# TestRig.net
KiCad netlist of a schematic drawn in EAGLE
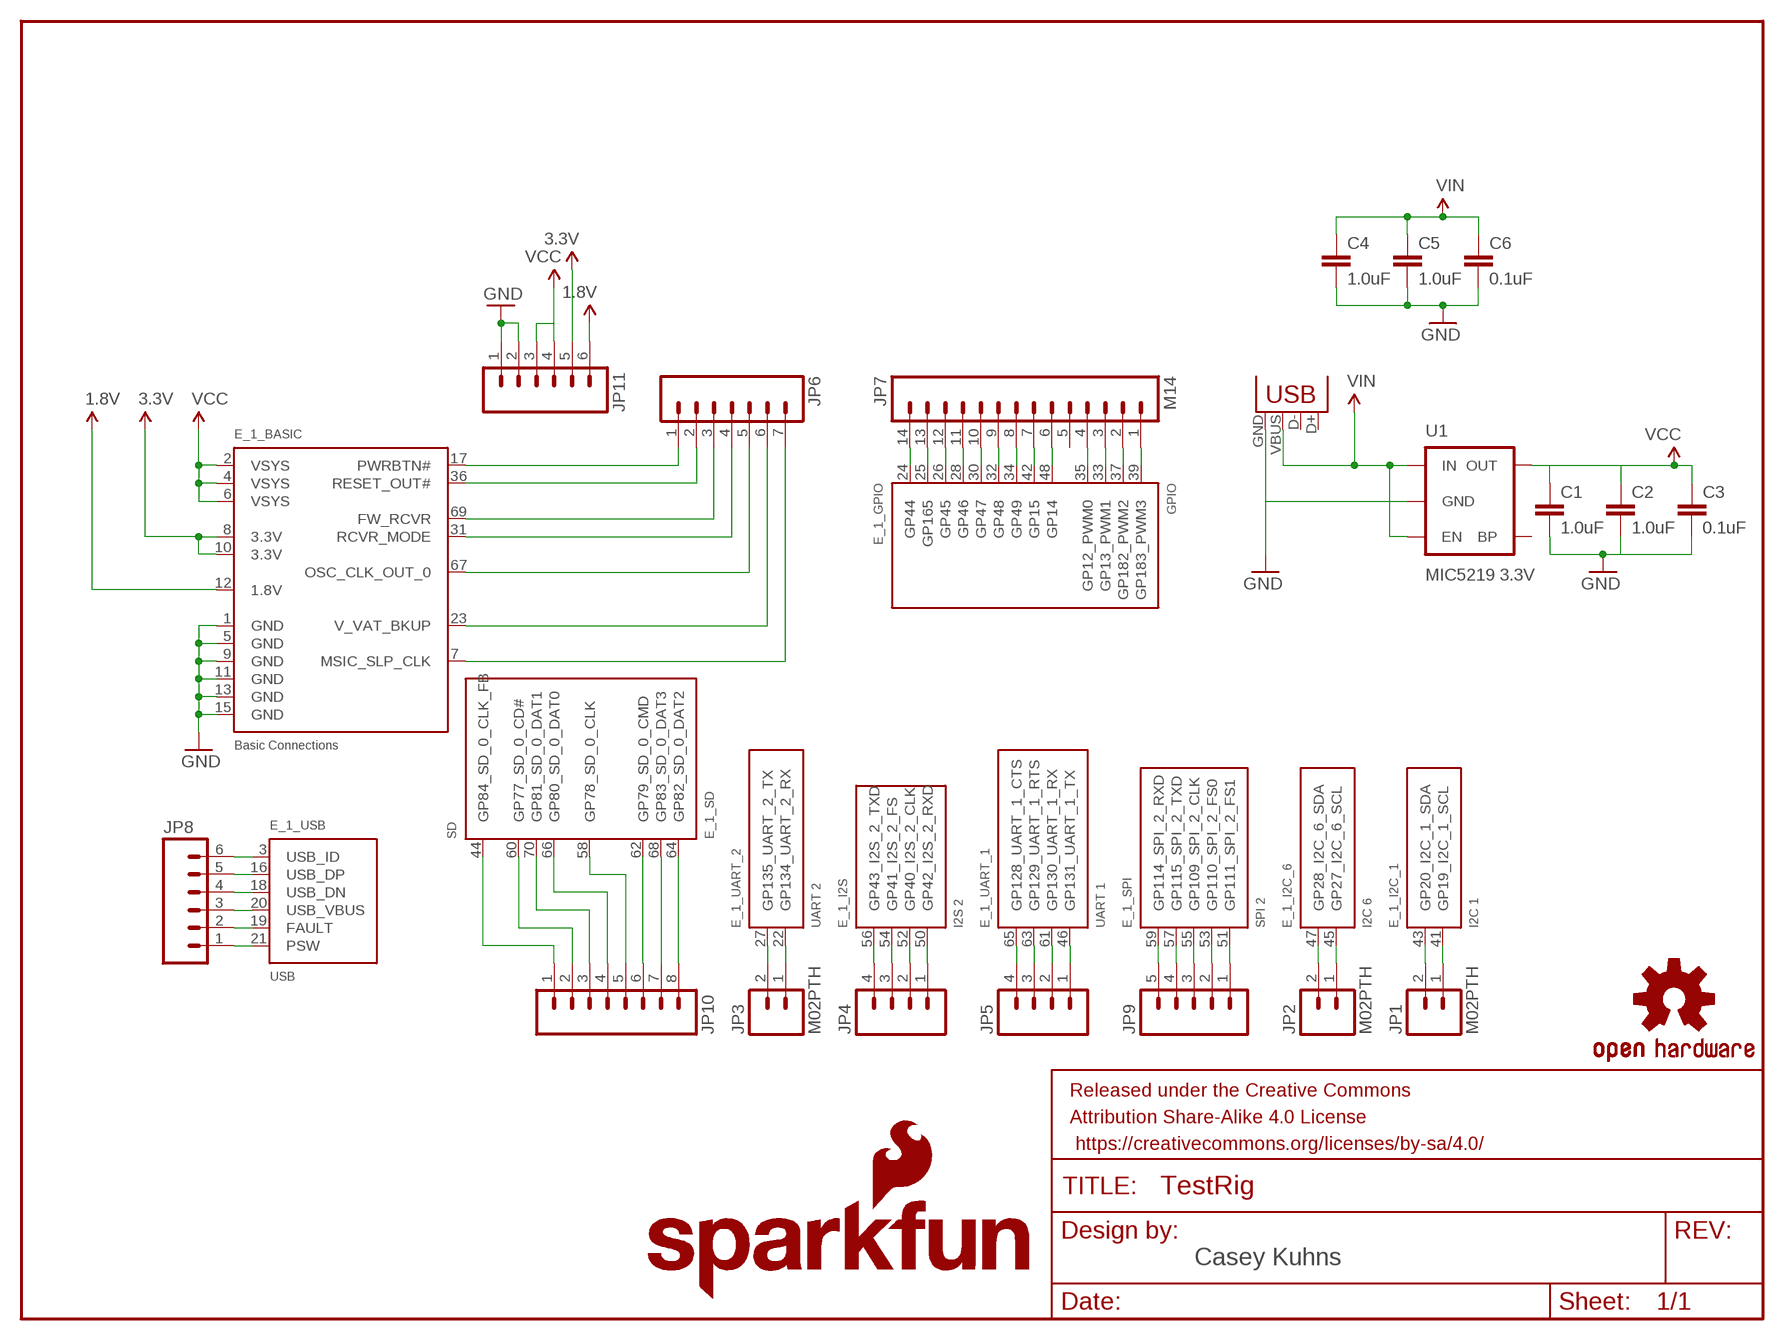
[diagram p0: schematic, sheet 1]

(export (version "E")
  (design (tool "Eeschema 10.0.6"))
  (components
    (comp (ref "C1")
      (value "1.0uF")
      (footprint "eagle-import:0805")
      (libsource (lib "eagle-import") (part "1.0UF-25V-+80/-20(0805)"))
    )
    (comp (ref "C2")
      (value "1.0uF")
      (footprint "eagle-import:0805")
      (libsource (lib "eagle-import") (part "1.0UF-25V-+80/-20(0805)"))
    )
    (comp (ref "C3")
      (value "0.1uF")
      (footprint "eagle-import:0603-CAP")
      (libsource (lib "eagle-import") (part "0.1UF-25V(+80/-20%)(0603)"))
    )
    (comp (ref "C4")
      (value "1.0uF")
      (footprint "eagle-import:0805")
      (libsource (lib "eagle-import") (part "1.0UF-25V-+80/-20(0805)"))
    )
    (comp (ref "C5")
      (value "1.0uF")
      (footprint "eagle-import:0805")
      (libsource (lib "eagle-import") (part "1.0UF-25V-+80/-20(0805)"))
    )
    (comp (ref "C6")
      (value "0.1uF")
      (footprint "eagle-import:0603-CAP")
      (libsource (lib "eagle-import") (part "0.1UF-25V(+80/-20%)(0603)"))
    )
    (comp (ref "E_1")
      (value "EDISON_CONNECTOR_SEGMENTED")
      (footprint "eagle-import:EDISON_DAUGHTER")
      (libsource (lib "eagle-import") (part "EDISON_CONNECTOR_SEGMENTED"))
    )
    (comp (ref "FRAME1")
      (value "FRAME-LETTER")
      (footprint "eagle-import:CREATIVE_COMMONS")
      (libsource (lib "eagle-import") (part "FRAME-LETTER"))
    )
    (comp (ref "JP1")
      (value "M02PTH")
      (footprint "eagle-import:1X02")
      (libsource (lib "eagle-import") (part "M02PTH"))
    )
    (comp (ref "JP2")
      (value "M02PTH")
      (footprint "eagle-import:1X02")
      (libsource (lib "eagle-import") (part "M02PTH"))
    )
    (comp (ref "JP3")
      (value "M02PTH")
      (footprint "eagle-import:1X02")
      (libsource (lib "eagle-import") (part "M02PTH"))
    )
    (comp (ref "JP4")
      (value "M04PTH")
      (footprint "eagle-import:1X04")
      (libsource (lib "eagle-import") (part "M04PTH"))
    )
    (comp (ref "JP5")
      (value "M04PTH")
      (footprint "eagle-import:1X04")
      (libsource (lib "eagle-import") (part "M04PTH"))
    )
    (comp (ref "JP6")
      (value "M07")
      (footprint "eagle-import:1X07")
      (libsource (lib "eagle-import") (part "M07"))
    )
    (comp (ref "JP7")
      (value "M14")
      (footprint "eagle-import:1X14")
      (libsource (lib "eagle-import") (part "M14"))
    )
    (comp (ref "JP8")
      (value "M06SIP")
      (footprint "eagle-import:1X06")
      (libsource (lib "eagle-import") (part "M06SIP"))
    )
    (comp (ref "JP9")
      (value "M05NO_SILK")
      (footprint "eagle-import:1X05_NO_SILK")
      (libsource (lib "eagle-import") (part "M05NO_SILK"))
    )
    (comp (ref "JP10")
      (value "M081X08")
      (footprint "eagle-import:1X08")
      (libsource (lib "eagle-import") (part "M081X08"))
    )
    (comp (ref "JP11")
      (value "M06SIP")
      (footprint "eagle-import:1X06")
      (libsource (lib "eagle-import") (part "M06SIP"))
    )
    (comp (ref "JP12")
      (value "USBSMD")
      (footprint "eagle-import:USB-MINIB")
      (libsource (lib "eagle-import") (part "USBSMD"))
    )
    (comp (ref "LOGO1")
      (value "SFE_LOGO_NAME_FLAME.1_INCH")
      (footprint "eagle-import:SFE_LOGO_NAME_FLAME_.1")
      (libsource (lib "eagle-import") (part "SFE_LOGO_NAME_FLAME.1_INCH"))
    )
    (comp (ref "LOGO2")
      (value "OSHW-LOGOS")
      (footprint "eagle-import:OSHW-LOGO-S")
      (libsource (lib "eagle-import") (part "OSHW-LOGOS"))
    )
    (comp (ref "U1")
      (value "MIC5219 3.3V")
      (footprint "eagle-import:SOT23-5")
      (libsource (lib "eagle-import") (part "V_REG_MIC52193.3V"))
    )
  )
  (nets
    (net (code "1") (name "1.8V") (class "Default")
      (node (ref "E_1") (pin "12") (pinfunction "1.8V_12") (pintype "bidirectional"))
      (node (ref "JP11") (pin "6") (pinfunction "6_6") (pintype "passive"))
    )
    (net (code "2") (name "3.3V") (class "Default")
      (node (ref "E_1") (pin "10") (pinfunction "3.3V_10") (pintype "bidirectional"))
      (node (ref "E_1") (pin "8") (pinfunction "3.3V_8") (pintype "bidirectional"))
      (node (ref "JP11") (pin "5") (pinfunction "5_5") (pintype "passive"))
    )
    (net (code "3") (name "GND") (class "Default")
      (node (ref "C1") (pin "2") (pinfunction "2_2") (pintype "passive"))
      (node (ref "C2") (pin "2") (pinfunction "2_2") (pintype "passive"))
      (node (ref "C3") (pin "2") (pinfunction "2_2") (pintype "passive"))
      (node (ref "C4") (pin "2") (pinfunction "2_2") (pintype "passive"))
      (node (ref "C5") (pin "2") (pinfunction "2_2") (pintype "passive"))
      (node (ref "C6") (pin "2") (pinfunction "2_2") (pintype "passive"))
      (node (ref "E_1") (pin "1") (pinfunction "GND_1") (pintype "bidirectional"))
      (node (ref "E_1") (pin "11") (pinfunction "GND_11") (pintype "bidirectional"))
      (node (ref "E_1") (pin "13") (pinfunction "GND_13") (pintype "bidirectional"))
      (node (ref "E_1") (pin "15") (pinfunction "GND_15") (pintype "bidirectional"))
      (node (ref "E_1") (pin "5") (pinfunction "GND_5") (pintype "bidirectional"))
      (node (ref "E_1") (pin "9") (pinfunction "GND_9") (pintype "bidirectional"))
      (node (ref "JP11") (pin "1") (pinfunction "1_1") (pintype "passive"))
      (node (ref "JP11") (pin "2") (pinfunction "2_2") (pintype "passive"))
      (node (ref "JP12") (pin "GND") (pinfunction "GND_GND") (pintype "bidirectional"))
      (node (ref "U1") (pin "2") (pinfunction "GND_2") (pintype "input"))
    )
    (net (code "4") (name "Net-(E_1A-FW_RCVR)") (class "Default")
      (node (ref "E_1") (pin "69") (pinfunction "FW_RCVR_69") (pintype "bidirectional"))
      (node (ref "JP6") (pin "3") (pinfunction "3_3") (pintype "passive"))
    )
    (net (code "5") (name "Net-(E_1A-MSIC_SLP_CLK)") (class "Default")
      (node (ref "E_1") (pin "7") (pinfunction "MSIC_SLP_CLK_7") (pintype "bidirectional"))
      (node (ref "JP6") (pin "7") (pinfunction "7_7") (pintype "passive"))
    )
    (net (code "6") (name "Net-(E_1A-OSC_CLK_OUT_0)") (class "Default")
      (node (ref "E_1") (pin "67") (pinfunction "OSC_CLK_OUT_0_67") (pintype "bidirectional"))
      (node (ref "JP6") (pin "5") (pinfunction "5_5") (pintype "passive"))
    )
    (net (code "7") (name "Net-(E_1A-PWRBTN#)") (class "Default")
      (node (ref "E_1") (pin "17") (pinfunction "PWRBTN#_17") (pintype "bidirectional"))
      (node (ref "JP6") (pin "1") (pinfunction "1_1") (pintype "passive"))
    )
    (net (code "8") (name "Net-(E_1A-RCVR_MODE)") (class "Default")
      (node (ref "E_1") (pin "31") (pinfunction "RCVR_MODE_31") (pintype "bidirectional"))
      (node (ref "JP6") (pin "4") (pinfunction "4_4") (pintype "passive"))
    )
    (net (code "9") (name "Net-(E_1A-RESET_OUT#)") (class "Default")
      (node (ref "E_1") (pin "36") (pinfunction "RESET_OUT#_36") (pintype "bidirectional"))
      (node (ref "JP6") (pin "2") (pinfunction "2_2") (pintype "passive"))
    )
    (net (code "10") (name "Net-(E_1A-V_VAT_BKUP)") (class "Default")
      (node (ref "E_1") (pin "23") (pinfunction "V_VAT_BKUP_23") (pintype "bidirectional"))
      (node (ref "JP6") (pin "6") (pinfunction "6_6") (pintype "passive"))
    )
    (net (code "11") (name "Net-(E_1B-GP12_PWM0)") (class "Default")
      (node (ref "E_1") (pin "35") (pinfunction "GP12_PWM0_35") (pintype "bidirectional"))
      (node (ref "JP7") (pin "4") (pinfunction "4_4") (pintype "passive"))
    )
    (net (code "12") (name "Net-(E_1B-GP13_PWM1)") (class "Default")
      (node (ref "E_1") (pin "33") (pinfunction "GP13_PWM1_33") (pintype "bidirectional"))
      (node (ref "JP7") (pin "3") (pinfunction "3_3") (pintype "passive"))
    )
    (net (code "13") (name "Net-(E_1B-GP14)") (class "Default")
      (node (ref "E_1") (pin "48") (pinfunction "GP14_48") (pintype "bidirectional"))
      (node (ref "JP7") (pin "6") (pinfunction "6_6") (pintype "passive"))
    )
    (net (code "14") (name "Net-(E_1B-GP15)") (class "Default")
      (node (ref "E_1") (pin "42") (pinfunction "GP15_42") (pintype "bidirectional"))
      (node (ref "JP7") (pin "7") (pinfunction "7_7") (pintype "passive"))
    )
    (net (code "15") (name "Net-(E_1B-GP44)") (class "Default")
      (node (ref "E_1") (pin "24") (pinfunction "GP44_24") (pintype "bidirectional"))
      (node (ref "JP7") (pin "14") (pinfunction "14_14") (pintype "passive"))
    )
    (net (code "16") (name "Net-(E_1B-GP45)") (class "Default")
      (node (ref "E_1") (pin "26") (pinfunction "GP45_26") (pintype "bidirectional"))
      (node (ref "JP7") (pin "12") (pinfunction "12_12") (pintype "passive"))
    )
    (net (code "17") (name "Net-(E_1B-GP46)") (class "Default")
      (node (ref "E_1") (pin "28") (pinfunction "GP46_28") (pintype "bidirectional"))
      (node (ref "JP7") (pin "11") (pinfunction "11_11") (pintype "passive"))
    )
    (net (code "18") (name "Net-(E_1B-GP47)") (class "Default")
      (node (ref "E_1") (pin "30") (pinfunction "GP47_30") (pintype "bidirectional"))
      (node (ref "JP7") (pin "10") (pinfunction "10_10") (pintype "passive"))
    )
    (net (code "19") (name "Net-(E_1B-GP48)") (class "Default")
      (node (ref "E_1") (pin "32") (pinfunction "GP48_32") (pintype "bidirectional"))
      (node (ref "JP7") (pin "9") (pinfunction "9_9") (pintype "passive"))
    )
    (net (code "20") (name "Net-(E_1B-GP49)") (class "Default")
      (node (ref "E_1") (pin "34") (pinfunction "GP49_34") (pintype "bidirectional"))
      (node (ref "JP7") (pin "8") (pinfunction "8_8") (pintype "passive"))
    )
    (net (code "21") (name "Net-(E_1B-GP165)") (class "Default")
      (node (ref "E_1") (pin "25") (pinfunction "GP165_25") (pintype "bidirectional"))
      (node (ref "JP7") (pin "13") (pinfunction "13_13") (pintype "passive"))
    )
    (net (code "22") (name "Net-(E_1B-GP182_PWM2)") (class "Default")
      (node (ref "E_1") (pin "37") (pinfunction "GP182_PWM2_37") (pintype "bidirectional"))
      (node (ref "JP7") (pin "2") (pinfunction "2_2") (pintype "passive"))
    )
    (net (code "23") (name "Net-(E_1B-GP183_PWM3)") (class "Default")
      (node (ref "E_1") (pin "39") (pinfunction "GP183_PWM3_39") (pintype "bidirectional"))
      (node (ref "JP7") (pin "1") (pinfunction "1_1") (pintype "passive"))
    )
    (net (code "24") (name "Net-(E_1C-GP19_I2C_1_SCL)") (class "Default")
      (node (ref "E_1") (pin "41") (pinfunction "GP19_I2C_1_SCL_41") (pintype "bidirectional"))
      (node (ref "JP1") (pin "1") (pinfunction "1_1") (pintype "passive"))
    )
    (net (code "25") (name "Net-(E_1C-GP20_I2C_1_SDA)") (class "Default")
      (node (ref "E_1") (pin "43") (pinfunction "GP20_I2C_1_SDA_43") (pintype "bidirectional"))
      (node (ref "JP1") (pin "2") (pinfunction "2_2") (pintype "passive"))
    )
    (net (code "26") (name "Net-(E_1D-GP27_I2C_6_SCL)") (class "Default")
      (node (ref "E_1") (pin "45") (pinfunction "GP27_I2C_6_SCL_45") (pintype "bidirectional"))
      (node (ref "JP2") (pin "1") (pinfunction "1_1") (pintype "passive"))
    )
    (net (code "27") (name "Net-(E_1D-GP28_I2C_6_SDA)") (class "Default")
      (node (ref "E_1") (pin "47") (pinfunction "GP28_I2C_6_SDA_47") (pintype "bidirectional"))
      (node (ref "JP2") (pin "2") (pinfunction "2_2") (pintype "passive"))
    )
    (net (code "28") (name "Net-(E_1E-GP40_I2S_2_CLK)") (class "Default")
      (node (ref "E_1") (pin "52") (pinfunction "GP40_I2S_2_CLK_52") (pintype "bidirectional"))
      (node (ref "JP4") (pin "2") (pinfunction "2_2") (pintype "passive"))
    )
    (net (code "29") (name "Net-(E_1E-GP41_I2S_2_FS)") (class "Default")
      (node (ref "E_1") (pin "54") (pinfunction "GP41_I2S_2_FS_54") (pintype "bidirectional"))
      (node (ref "JP4") (pin "3") (pinfunction "3_3") (pintype "passive"))
    )
    (net (code "30") (name "Net-(E_1E-GP42_I2S_2_RXD)") (class "Default")
      (node (ref "E_1") (pin "50") (pinfunction "GP42_I2S_2_RXD_50") (pintype "bidirectional"))
      (node (ref "JP4") (pin "1") (pinfunction "1_1") (pintype "passive"))
    )
    (net (code "31") (name "Net-(E_1E-GP43_I2S_2_TXD)") (class "Default")
      (node (ref "E_1") (pin "56") (pinfunction "GP43_I2S_2_TXD_56") (pintype "bidirectional"))
      (node (ref "JP4") (pin "4") (pinfunction "4_4") (pintype "passive"))
    )
    (net (code "32") (name "Net-(E_1F-GP77_SD_0_CD#)") (class "Default")
      (node (ref "E_1") (pin "60") (pinfunction "GP77_SD_0_CD#_60") (pintype "bidirectional"))
      (node (ref "JP10") (pin "2") (pinfunction "2_2") (pintype "passive"))
    )
    (net (code "33") (name "Net-(E_1F-GP78_SD_0_CLK)") (class "Default")
      (node (ref "E_1") (pin "58") (pinfunction "GP78_SD_0_CLK_58") (pintype "bidirectional"))
      (node (ref "JP10") (pin "5") (pinfunction "5_5") (pintype "passive"))
    )
    (net (code "34") (name "Net-(E_1F-GP79_SD_0_CMD)") (class "Default")
      (node (ref "E_1") (pin "62") (pinfunction "GP79_SD_0_CMD_62") (pintype "bidirectional"))
      (node (ref "JP10") (pin "6") (pinfunction "6_6") (pintype "passive"))
    )
    (net (code "35") (name "Net-(E_1F-GP80_SD_0_DAT0)") (class "Default")
      (node (ref "E_1") (pin "66") (pinfunction "GP80_SD_0_DAT0_66") (pintype "bidirectional"))
      (node (ref "JP10") (pin "4") (pinfunction "4_4") (pintype "passive"))
    )
    (net (code "36") (name "Net-(E_1F-GP81_SD_0_DAT1)") (class "Default")
      (node (ref "E_1") (pin "70") (pinfunction "GP81_SD_0_DAT1_70") (pintype "bidirectional"))
      (node (ref "JP10") (pin "3") (pinfunction "3_3") (pintype "passive"))
    )
    (net (code "37") (name "Net-(E_1F-GP82_SD_0_DAT2)") (class "Default")
      (node (ref "E_1") (pin "64") (pinfunction "GP82_SD_0_DAT2_64") (pintype "bidirectional"))
      (node (ref "JP10") (pin "8") (pinfunction "8_8") (pintype "passive"))
    )
    (net (code "38") (name "Net-(E_1F-GP83_SD_0_DAT3)") (class "Default")
      (node (ref "E_1") (pin "68") (pinfunction "GP83_SD_0_DAT3_68") (pintype "bidirectional"))
      (node (ref "JP10") (pin "7") (pinfunction "7_7") (pintype "passive"))
    )
    (net (code "39") (name "Net-(E_1F-GP84_SD_0_CLK_FB)") (class "Default")
      (node (ref "E_1") (pin "44") (pinfunction "GP84_SD_0_CLK_FB_44") (pintype "bidirectional"))
      (node (ref "JP10") (pin "1") (pinfunction "1_1") (pintype "passive"))
    )
    (net (code "40") (name "Net-(E_1G-GP109_SPI_2_CLK)") (class "Default")
      (node (ref "E_1") (pin "55") (pinfunction "GP109_SPI_2_CLK_55") (pintype "bidirectional"))
      (node (ref "JP9") (pin "3") (pinfunction "3_3") (pintype "passive"))
    )
    (net (code "41") (name "Net-(E_1G-GP110_SPI_2_FS0)") (class "Default")
      (node (ref "E_1") (pin "53") (pinfunction "GP110_SPI_2_FS0_53") (pintype "bidirectional"))
      (node (ref "JP9") (pin "2") (pinfunction "2_2") (pintype "passive"))
    )
    (net (code "42") (name "Net-(E_1G-GP111_SPI_2_FS1)") (class "Default")
      (node (ref "E_1") (pin "51") (pinfunction "GP111_SPI_2_FS1_51") (pintype "bidirectional"))
      (node (ref "JP9") (pin "1") (pinfunction "1_1") (pintype "passive"))
    )
    (net (code "43") (name "Net-(E_1G-GP114_SPI_2_RXD)") (class "Default")
      (node (ref "E_1") (pin "59") (pinfunction "GP114_SPI_2_RXD_59") (pintype "bidirectional"))
      (node (ref "JP9") (pin "5") (pinfunction "5_5") (pintype "passive"))
    )
    (net (code "44") (name "Net-(E_1G-GP115_SPI_2_TXD)") (class "Default")
      (node (ref "E_1") (pin "57") (pinfunction "GP115_SPI_2_TXD_57") (pintype "bidirectional"))
      (node (ref "JP9") (pin "4") (pinfunction "4_4") (pintype "passive"))
    )
    (net (code "45") (name "Net-(E_1H-GP128_UART_1_CTS)") (class "Default")
      (node (ref "E_1") (pin "65") (pinfunction "GP128_UART_1_CTS_65") (pintype "bidirectional"))
      (node (ref "JP5") (pin "4") (pinfunction "4_4") (pintype "passive"))
    )
    (net (code "46") (name "Net-(E_1H-GP129_UART_1_RTS)") (class "Default")
      (node (ref "E_1") (pin "63") (pinfunction "GP129_UART_1_RTS_63") (pintype "bidirectional"))
      (node (ref "JP5") (pin "3") (pinfunction "3_3") (pintype "passive"))
    )
    (net (code "47") (name "Net-(E_1H-GP130_UART_1_RX)") (class "Default")
      (node (ref "E_1") (pin "61") (pinfunction "GP130_UART_1_RX_61") (pintype "bidirectional"))
      (node (ref "JP5") (pin "2") (pinfunction "2_2") (pintype "passive"))
    )
    (net (code "48") (name "Net-(E_1H-GP131_UART_1_TX)") (class "Default")
      (node (ref "E_1") (pin "46") (pinfunction "GP131_UART_1_TX_46") (pintype "bidirectional"))
      (node (ref "JP5") (pin "1") (pinfunction "1_1") (pintype "passive"))
    )
    (net (code "49") (name "Net-(E_1I-GP134_UART_2_RX)") (class "Default")
      (node (ref "E_1") (pin "22") (pinfunction "GP134_UART_2_RX_22") (pintype "bidirectional"))
      (node (ref "JP3") (pin "1") (pinfunction "1_1") (pintype "passive"))
    )
    (net (code "50") (name "Net-(E_1I-GP135_UART_2_TX)") (class "Default")
      (node (ref "E_1") (pin "27") (pinfunction "GP135_UART_2_TX_27") (pintype "bidirectional"))
      (node (ref "JP3") (pin "2") (pinfunction "2_2") (pintype "passive"))
    )
    (net (code "51") (name "Net-(E_1J-FAULT)") (class "Default")
      (node (ref "E_1") (pin "19") (pinfunction "FAULT_19") (pintype "bidirectional"))
      (node (ref "JP8") (pin "2") (pinfunction "2_2") (pintype "passive"))
    )
    (net (code "52") (name "Net-(E_1J-PSW)") (class "Default")
      (node (ref "E_1") (pin "21") (pinfunction "PSW_21") (pintype "bidirectional"))
      (node (ref "JP8") (pin "1") (pinfunction "1_1") (pintype "passive"))
    )
    (net (code "53") (name "Net-(E_1J-USB_DN)") (class "Default")
      (node (ref "E_1") (pin "18") (pinfunction "USB_DN_18") (pintype "bidirectional"))
      (node (ref "JP8") (pin "4") (pinfunction "4_4") (pintype "passive"))
    )
    (net (code "54") (name "Net-(E_1J-USB_DP)") (class "Default")
      (node (ref "E_1") (pin "16") (pinfunction "USB_DP_16") (pintype "bidirectional"))
      (node (ref "JP8") (pin "5") (pinfunction "5_5") (pintype "passive"))
    )
    (net (code "55") (name "Net-(E_1J-USB_ID)") (class "Default")
      (node (ref "E_1") (pin "3") (pinfunction "USB_ID_3") (pintype "bidirectional"))
      (node (ref "JP8") (pin "6") (pinfunction "6_6") (pintype "passive"))
    )
    (net (code "56") (name "Net-(E_1J-USB_VBUS)") (class "Default")
      (node (ref "E_1") (pin "20") (pinfunction "USB_VBUS_20") (pintype "bidirectional"))
      (node (ref "JP8") (pin "3") (pinfunction "3_3") (pintype "passive"))
    )
    (net (code "57") (name "VCC") (class "Default")
      (node (ref "C1") (pin "1") (pinfunction "1_1") (pintype "passive"))
      (node (ref "C2") (pin "1") (pinfunction "1_1") (pintype "passive"))
      (node (ref "C3") (pin "1") (pinfunction "1_1") (pintype "passive"))
      (node (ref "E_1") (pin "2") (pinfunction "VSYS_2") (pintype "bidirectional"))
      (node (ref "E_1") (pin "4") (pinfunction "VSYS_4") (pintype "bidirectional"))
      (node (ref "E_1") (pin "6") (pinfunction "VSYS_6") (pintype "bidirectional"))
      (node (ref "JP11") (pin "3") (pinfunction "3_3") (pintype "passive"))
      (node (ref "JP11") (pin "4") (pinfunction "4_4") (pintype "passive"))
      (node (ref "U1") (pin "5") (pinfunction "OUT_5") (pintype "passive"))
    )
    (net (code "58") (name "VIN") (class "Default")
      (node (ref "C4") (pin "1") (pinfunction "1_1") (pintype "passive"))
      (node (ref "C5") (pin "1") (pinfunction "1_1") (pintype "passive"))
      (node (ref "C6") (pin "1") (pinfunction "1_1") (pintype "passive"))
      (node (ref "JP12") (pin "VBUS") (pinfunction "VBUS_VBUS") (pintype "bidirectional"))
      (node (ref "U1") (pin "1") (pinfunction "IN_1") (pintype "input"))
      (node (ref "U1") (pin "3") (pinfunction "EN_3") (pintype "input"))
    )
    (net (code "59") (name "unconnected-(JP7-Pad5)") (class "Default")
      (node (ref "JP7") (pin "5") (pinfunction "5_5") (pintype "passive"))
    )
    (net (code "60") (name "unconnected-(JP12-PadD+)") (class "Default")
      (node (ref "JP12") (pin "D+") (pinfunction "D+_D+") (pintype "bidirectional"))
    )
    (net (code "61") (name "unconnected-(JP12-PadD-)") (class "Default")
      (node (ref "JP12") (pin "D-") (pinfunction "D-_D-") (pintype "bidirectional"))
    )
    (net (code "62") (name "unconnected-(U1-BP-Pad4)") (class "Default")
      (node (ref "U1") (pin "4") (pinfunction "BP_4") (pintype "input"))
    )
  )
)
